# Comunicaciones.net
KiCad netlist of a schematic drawn in Altium Designer
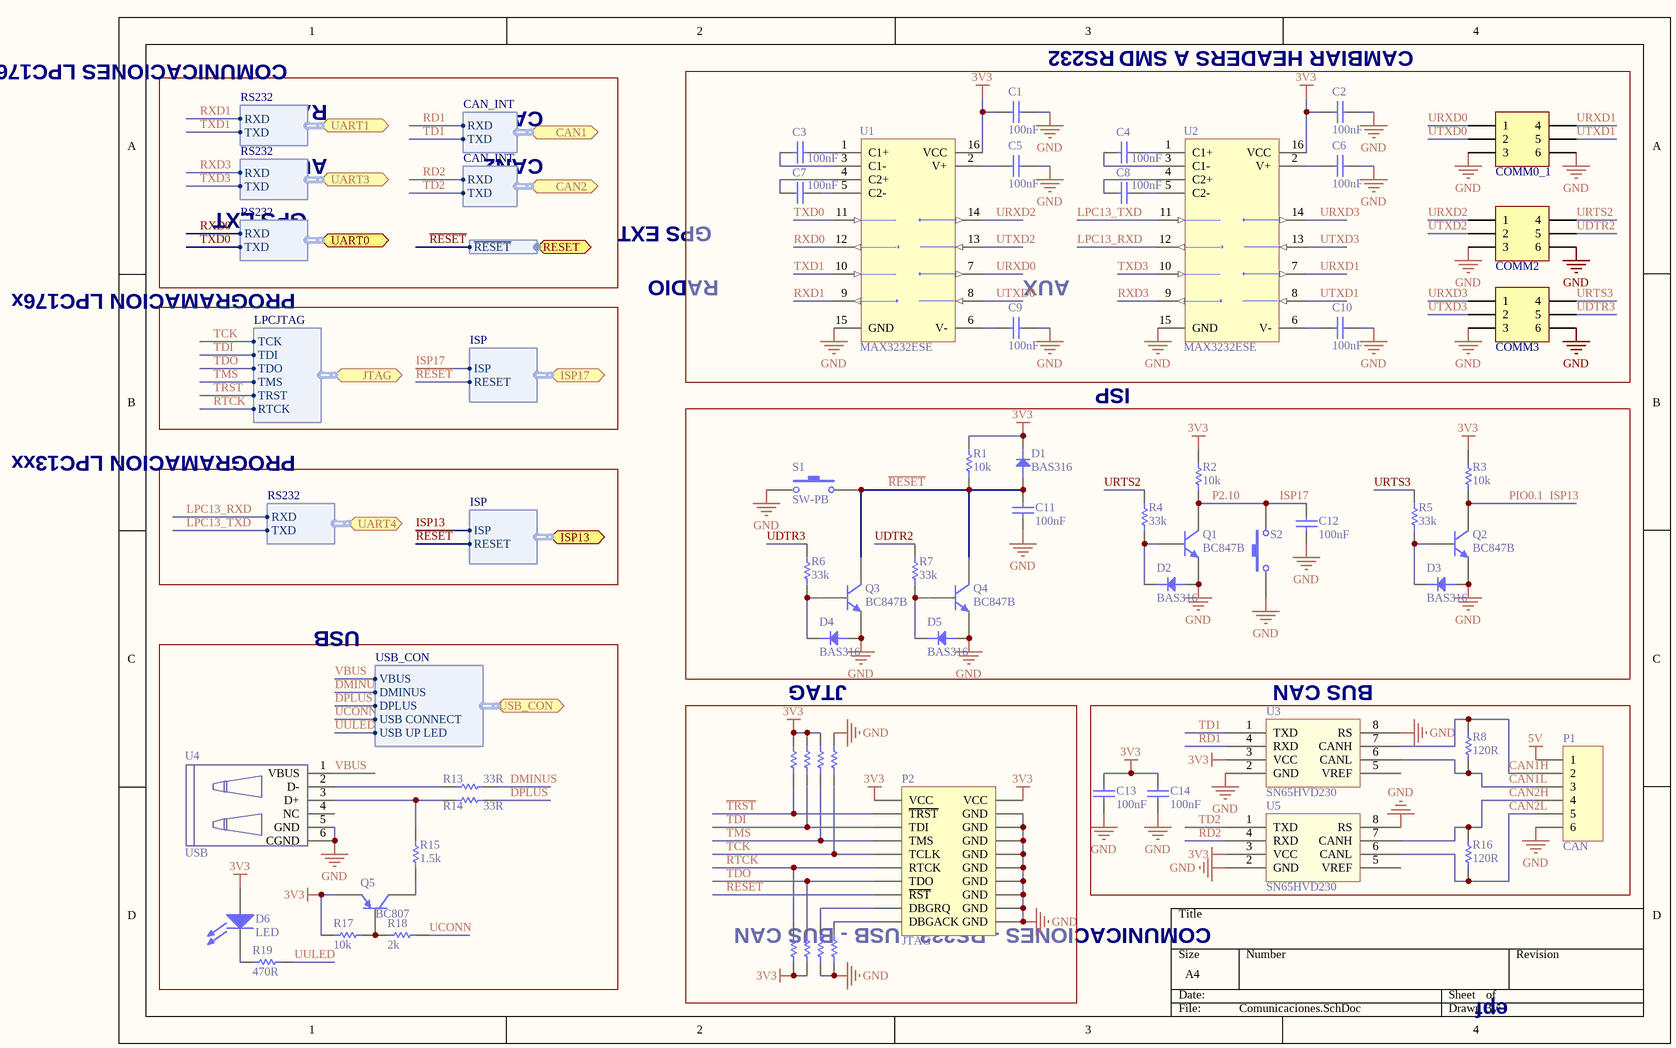
[diagram p0: Comunicaciones.SchDoc]

(export (version "E")
  (design (tool "Eeschema 10.0.6"))
  (components
    (comp (ref "C1")
      (value "100nF")
      (footprint "CAP0402")
      (fields (field (name "Comment") "Capacitor"))
      (libsource (lib "epf") (part "Cap"))
    )
    (comp (ref "C2")
      (value "100nF")
      (footprint "CAP0402")
      (fields (field (name "Comment") "Capacitor"))
      (libsource (lib "epf") (part "Cap"))
    )
    (comp (ref "C3")
      (value "100nF")
      (footprint "CAP0402")
      (fields (field (name "Comment") "Capacitor"))
      (libsource (lib "epf") (part "Cap"))
    )
    (comp (ref "C4")
      (value "100nF")
      (footprint "CAP0402")
      (fields (field (name "Comment") "Capacitor"))
      (libsource (lib "epf") (part "Cap"))
    )
    (comp (ref "C5")
      (value "100nF")
      (footprint "CAP0402")
      (fields (field (name "Comment") "Capacitor"))
      (libsource (lib "epf") (part "Cap"))
    )
    (comp (ref "C6")
      (value "100nF")
      (footprint "CAP0402")
      (fields (field (name "Comment") "Capacitor"))
      (libsource (lib "epf") (part "Cap"))
    )
    (comp (ref "C7")
      (value "100nF")
      (footprint "CAP0402")
      (fields (field (name "Comment") "Capacitor"))
      (libsource (lib "epf") (part "Cap"))
    )
    (comp (ref "C8")
      (value "100nF")
      (footprint "CAP0402")
      (fields (field (name "Comment") "Capacitor"))
      (libsource (lib "epf") (part "Cap"))
    )
    (comp (ref "C9")
      (value "100nF")
      (footprint "CAP0402")
      (fields (field (name "Comment") "Capacitor"))
      (libsource (lib "epf") (part "Cap"))
    )
    (comp (ref "C10")
      (value "100nF")
      (footprint "CAP0402")
      (fields (field (name "Comment") "Capacitor"))
      (libsource (lib "epf") (part "Cap"))
    )
    (comp (ref "C11")
      (value "100nF")
      (footprint "CAP0402")
      (fields (field (name "Comment") "Capacitor"))
      (libsource (lib "epf") (part "Cap"))
    )
    (comp (ref "C12")
      (value "100nF")
      (footprint "CAP0402")
      (fields (field (name "Comment") "Capacitor"))
      (libsource (lib "epf") (part "Cap"))
    )
    (comp (ref "C13")
      (value "100nF")
      (footprint "CAP0402")
      (fields (field (name "Comment") "Capacitor"))
      (libsource (lib "epf") (part "Cap"))
    )
    (comp (ref "C14")
      (value "100nF")
      (footprint "CAP0402")
      (fields (field (name "Comment") "Capacitor"))
      (libsource (lib "epf") (part "Cap"))
    )
    (comp (ref "COMM0_1")
      (value "AP_COMM")
      (footprint "HDR2X3_CEN")
      (description "Header, 3-Pin, Dual row")
      (fields (field (name "PUBLISHER") "Altium Limited"))
      (libsource (lib "epf") (part "AP_COMM"))
    )
    (comp (ref "COMM2")
      (value "AP_COMM")
      (footprint "HDR2X3_CEN")
      (description "Header, 3-Pin, Dual row")
      (fields (field (name "PUBLISHER") "Altium Limited"))
      (libsource (lib "epf") (part "AP_COMM"))
    )
    (comp (ref "COMM3")
      (value "AP_COMM")
      (footprint "HDR2X3_CEN")
      (description "Header, 3-Pin, Dual row")
      (fields (field (name "PUBLISHER") "Altium Limited"))
      (libsource (lib "epf") (part "AP_COMM"))
    )
    (comp (ref "D1") (value "BAS316") (footprint "SOD-323") (libsource (lib "epf") (part "BAS316")))
    (comp (ref "D2") (value "BAS316") (footprint "SOD-323") (libsource (lib "epf") (part "BAS316")))
    (comp (ref "D3") (value "BAS316") (footprint "SOD-323") (libsource (lib "epf") (part "BAS316")))
    (comp (ref "D4") (value "BAS316") (footprint "SOD-323") (libsource (lib "epf") (part "BAS316")))
    (comp (ref "D5") (value "BAS316") (footprint "SOD-323") (libsource (lib "epf") (part "BAS316")))
    (comp (ref "D6") (value "LED") (footprint "PLCC-2Rojo") (libsource (lib "epf") (part "LED1")))
    (comp (ref "P1")
      (value "CAN")
      (footprint "HDR1X6")
      (description "Header, 6-Pin")
      (fields (field (name "PUBLISHER") "Altium Limited"))
      (libsource (lib "epf") (part "CAN_Conn"))
    )
    (comp (ref "P2")
      (value "JTAG")
      (footprint "HDR2X10")
      (description "Header, 10-Pin, Dual row")
      (fields (field (name "PUBLISHER") "Altium Limited"))
      (libsource (lib "epf") (part "JTAG"))
    )
    (comp (ref "Q1")
      (value "BC847B")
      (footprint "SOT23")
      (description "NPN 100MHz")
      (libsource (lib "epf") (part "BC847B"))
    )
    (comp (ref "Q2")
      (value "BC847B")
      (footprint "SOT23")
      (description "NPN 100MHz")
      (libsource (lib "epf") (part "BC847B"))
    )
    (comp (ref "Q3")
      (value "BC847B")
      (footprint "SOT23")
      (description "NPN 100MHz")
      (libsource (lib "epf") (part "BC847B"))
    )
    (comp (ref "Q4")
      (value "BC847B")
      (footprint "SOT23")
      (description "NPN 100MHz")
      (libsource (lib "epf") (part "BC847B"))
    )
    (comp (ref "Q5")
      (value "BC807")
      (footprint "SOT23")
      (description "PNP 100MHz")
      (libsource (lib "epf") (part "BC807"))
    )
    (comp (ref "R1")
      (value "10k")
      (footprint "RES0402")
      (fields (field (name "Comment") "Resistor"))
      (libsource (lib "epf") (part "Res"))
    )
    (comp (ref "R2")
      (value "10k")
      (footprint "RES0402")
      (fields (field (name "Comment") "Resistor"))
      (libsource (lib "epf") (part "Res"))
    )
    (comp (ref "R3")
      (value "10k")
      (footprint "RES0402")
      (fields (field (name "Comment") "Resistor"))
      (libsource (lib "epf") (part "Res"))
    )
    (comp (ref "R4")
      (value "33k")
      (footprint "RES0402")
      (fields (field (name "Comment") "Resistor"))
      (libsource (lib "epf") (part "Res"))
    )
    (comp (ref "R5")
      (value "33k")
      (footprint "RES0402")
      (fields (field (name "Comment") "Resistor"))
      (libsource (lib "epf") (part "Res"))
    )
    (comp (ref "R6")
      (value "33k")
      (footprint "RES0402")
      (fields (field (name "Comment") "Resistor"))
      (libsource (lib "epf") (part "Res"))
    )
    (comp (ref "R7")
      (value "33k")
      (footprint "RES0402")
      (fields (field (name "Comment") "Resistor"))
      (libsource (lib "epf") (part "Res"))
    )
    (comp (ref "R8")
      (value "120R")
      (footprint "RES0402")
      (fields (field (name "Comment") "Resistor"))
      (libsource (lib "epf") (part "Res"))
    )
    (comp (ref "R9") (value "Resistor") (footprint "RES0402") (libsource (lib "epf") (part "Res")))
    (comp (ref "R10") (value "Resistor") (footprint "RES0402") (libsource (lib "epf") (part "Res")))
    (comp (ref "R11") (value "Resistor") (footprint "RES0402") (libsource (lib "epf") (part "Res")))
    (comp (ref "R12") (value "Resistor") (footprint "RES0402") (libsource (lib "epf") (part "Res")))
    (comp (ref "R13")
      (value "33R")
      (footprint "RES0402")
      (fields (field (name "Comment") "Resistor"))
      (libsource (lib "epf") (part "Res"))
    )
    (comp (ref "R14")
      (value "33R")
      (footprint "RES0402")
      (fields (field (name "Comment") "Resistor"))
      (libsource (lib "epf") (part "Res"))
    )
    (comp (ref "R15")
      (value "1.5k")
      (footprint "RES0402")
      (fields (field (name "Comment") "Resistor"))
      (libsource (lib "epf") (part "Res"))
    )
    (comp (ref "R16")
      (value "120R")
      (footprint "RES0402")
      (fields (field (name "Comment") "Resistor"))
      (libsource (lib "epf") (part "Res"))
    )
    (comp (ref "R17")
      (value "10k")
      (footprint "RES0402")
      (fields (field (name "Comment") "Resistor"))
      (libsource (lib "epf") (part "Res"))
    )
    (comp (ref "R18")
      (value "2k")
      (footprint "RES0402")
      (fields (field (name "Comment") "Resistor"))
      (libsource (lib "epf") (part "Res"))
    )
    (comp (ref "R19")
      (value "470R")
      (footprint "RES0402")
      (fields (field (name "Comment") "Resistor"))
      (libsource (lib "epf") (part "Res"))
    )
    (comp (ref "R20") (value "Resistor") (footprint "RES0402") (libsource (lib "epf") (part "Res")))
    (comp (ref "R21") (value "Resistor") (footprint "RES0402") (libsource (lib "epf") (part "Res")))
    (comp (ref "R22") (value "Resistor") (footprint "RES0402") (libsource (lib "epf") (part "Res")))
    (comp (ref "R23") (value "Resistor") (footprint "RES0402") (libsource (lib "epf") (part "Res")))
    (comp (ref "S1")
      (value "SW-PB")
      (footprint "SW-PB6mm - 2")
      (description "Switch")
      (fields (field (name "PUBLISHER") "Altium Limited"))
      (libsource (lib "epf") (part "SW-PB"))
    )
    (comp (ref "S2")
      (value "SW-PB")
      (footprint "SW-PB6mm - 2")
      (description "Switch")
      (fields (field (name "PUBLISHER") "Altium Limited"))
      (libsource (lib "epf") (part "SW-PB"))
    )
    (comp (ref "U1")
      (value "MAX3232ESE")
      (footprint "SOIC127P602-16BN")
      (libsource (lib "epf") (part "MAX3232ESE+"))
    )
    (comp (ref "U2")
      (value "MAX3232ESE")
      (footprint "SOIC127P602-16BN")
      (libsource (lib "epf") (part "MAX3232ESE+"))
    )
    (comp (ref "U3")
      (value "SN65HVD230")
      (footprint "SOIC127P600-8CN")
      (description "3.3-V CAN TRANSCEIVERS")
      (libsource (lib "epf") (part "SN65HVD230"))
    )
    (comp (ref "U4") (value "USB") (footprint "USB/SM0.8-6H5") (libsource (lib "epf") (part "USB-miniB")))
    (comp (ref "U5")
      (value "SN65HVD230")
      (footprint "SOIC127P600-8CN")
      (description "3.3-V CAN TRANSCEIVERS")
      (libsource (lib "epf") (part "SN65HVD230"))
    )
  )
  (nets
    (net (code "6") (name "/CAN1H") (class "Default")
      (node (ref "P1") (pin "2") (pinfunction "2_2") (pintype "passive"))
      (node (ref "R8") (pin "1") (pinfunction "1_1") (pintype "passive"))
      (node (ref "U3") (pin "7") (pinfunction "CANH_7") (pintype "passive"))
    )
    (net (code "7") (name "/CAN1L") (class "Default")
      (node (ref "P1") (pin "3") (pinfunction "3_3") (pintype "passive"))
      (node (ref "R8") (pin "2") (pinfunction "2_2") (pintype "passive"))
      (node (ref "U3") (pin "6") (pinfunction "CANL_6") (pintype "passive"))
    )
    (net (code "8") (name "/CAN2H") (class "Default")
      (node (ref "P1") (pin "4") (pinfunction "4_4") (pintype "passive"))
      (node (ref "R16") (pin "1") (pinfunction "1_1") (pintype "passive"))
      (node (ref "U5") (pin "7") (pinfunction "CANH_7") (pintype "passive"))
    )
    (net (code "9") (name "/CAN2L") (class "Default")
      (node (ref "P1") (pin "5") (pinfunction "5_5") (pintype "passive"))
      (node (ref "R16") (pin "2") (pinfunction "2_2") (pintype "passive"))
      (node (ref "U5") (pin "6") (pinfunction "CANL_6") (pintype "passive"))
    )
    (net (code "10") (name "/DMINUS") (class "Default")
      (node (ref "R13") (pin "2") (pinfunction "2_2") (pintype "passive"))
    )
    (net (code "11") (name "/DPLUS") (class "Default")
      (node (ref "R14") (pin "2") (pinfunction "2_2") (pintype "passive"))
    )
    (net (code "12") (name "/ISP13") (class "Default")
      (node (ref "Q2") (pin "3") (pinfunction "C_3") (pintype "passive"))
      (node (ref "R3") (pin "1") (pinfunction "1_1") (pintype "passive"))
    )
    (net (code "13") (name "/ISP17") (class "Default")
      (node (ref "C12") (pin "1") (pinfunction "1_1") (pintype "passive"))
      (node (ref "Q1") (pin "3") (pinfunction "C_3") (pintype "passive"))
      (node (ref "R2") (pin "1") (pinfunction "1_1") (pintype "passive"))
      (node (ref "S2") (pin "2") (pinfunction "2_2") (pintype "passive"))
    )
    (net (code "14") (name "/LPC13_RXD") (class "Default")
      (node (ref "U2") (pin "12") (pinfunction "R1OUT_12") (pintype "output"))
    )
    (net (code "15") (name "/LPC13_TXD") (class "Default")
      (node (ref "U2") (pin "11") (pinfunction "T1IN_11") (pintype "input"))
    )
    (net (code "16") (name "/RD1") (class "Default")
      (node (ref "U3") (pin "4") (pinfunction "RXD_4") (pintype "passive"))
    )
    (net (code "17") (name "/RD2") (class "Default")
      (node (ref "U5") (pin "4") (pinfunction "RXD_4") (pintype "passive"))
    )
    (net (code "18") (name "/RESET") (class "Default")
      (node (ref "C11") (pin "1") (pinfunction "1_1") (pintype "passive"))
      (node (ref "D1") (pin "2") (pinfunction "A_2") (pintype "passive"))
      (node (ref "P2") (pin "15") (pinfunction "RST_15") (pintype "passive"))
      (node (ref "Q3") (pin "3") (pinfunction "C_3") (pintype "passive"))
      (node (ref "Q4") (pin "3") (pinfunction "C_3") (pintype "passive"))
      (node (ref "R1") (pin "1") (pinfunction "1_1") (pintype "passive"))
      (node (ref "S1") (pin "2") (pinfunction "2_2") (pintype "passive"))
    )
    (net (code "19") (name "/RTCK") (class "Default")
      (node (ref "P2") (pin "11") (pinfunction "RTCK_11") (pintype "passive"))
      (node (ref "R20") (pin "1") (pinfunction "1_1") (pintype "passive"))
    )
    (net (code "20") (name "/RXD0") (class "Default")
      (node (ref "U1") (pin "12") (pinfunction "R1OUT_12") (pintype "output"))
    )
    (net (code "21") (name "/RXD1") (class "Default")
      (node (ref "U1") (pin "9") (pinfunction "R2OUT_9") (pintype "output"))
    )
    (net (code "22") (name "/RXD3") (class "Default")
      (node (ref "U2") (pin "9") (pinfunction "R2OUT_9") (pintype "output"))
    )
    (net (code "23") (name "/TCK") (class "Default")
      (node (ref "P2") (pin "9") (pinfunction "TCLK_9") (pintype "passive"))
      (node (ref "R12") (pin "2") (pinfunction "2_2") (pintype "passive"))
    )
    (net (code "24") (name "/TD1") (class "Default")
      (node (ref "U3") (pin "1") (pinfunction "TXD_1") (pintype "passive"))
    )
    (net (code "25") (name "/TD2") (class "Default")
      (node (ref "U5") (pin "1") (pinfunction "TXD_1") (pintype "passive"))
    )
    (net (code "26") (name "/TDI") (class "Default")
      (node (ref "P2") (pin "5") (pinfunction "TDI_5") (pintype "passive"))
      (node (ref "R10") (pin "2") (pinfunction "2_2") (pintype "passive"))
    )
    (net (code "27") (name "/TDO") (class "Default")
      (node (ref "P2") (pin "13") (pinfunction "TDO_13") (pintype "passive"))
      (node (ref "R21") (pin "1") (pinfunction "1_1") (pintype "passive"))
    )
    (net (code "28") (name "/TMS") (class "Default")
      (node (ref "P2") (pin "7") (pinfunction "TMS_7") (pintype "passive"))
      (node (ref "R11") (pin "2") (pinfunction "2_2") (pintype "passive"))
    )
    (net (code "29") (name "/TRST") (class "Default")
      (node (ref "P2") (pin "3") (pinfunction "TRST_3") (pintype "passive"))
      (node (ref "R9") (pin "2") (pinfunction "2_2") (pintype "passive"))
    )
    (net (code "30") (name "/TXD0") (class "Default")
      (node (ref "U1") (pin "11") (pinfunction "T1IN_11") (pintype "input"))
    )
    (net (code "31") (name "/TXD1") (class "Default")
      (node (ref "U1") (pin "10") (pinfunction "T2IN_10") (pintype "input"))
    )
    (net (code "32") (name "/TXD3") (class "Default")
      (node (ref "U2") (pin "10") (pinfunction "T2IN_10") (pintype "input"))
    )
    (net (code "33") (name "/UCONN") (class "Default")
      (node (ref "R18") (pin "2") (pinfunction "2_2") (pintype "passive"))
    )
    (net (code "34") (name "/UDTR2") (class "Default")
      (node (ref "COMM2") (pin "5") (pinfunction "5_5") (pintype "passive"))
      (node (ref "R7") (pin "2") (pinfunction "2_2") (pintype "passive"))
    )
    (net (code "35") (name "/UDTR3") (class "Default")
      (node (ref "COMM3") (pin "5") (pinfunction "5_5") (pintype "passive"))
      (node (ref "R6") (pin "2") (pinfunction "2_2") (pintype "passive"))
    )
    (net (code "36") (name "/URTS2") (class "Default")
      (node (ref "COMM2") (pin "4") (pinfunction "4_4") (pintype "passive"))
      (node (ref "R4") (pin "2") (pinfunction "2_2") (pintype "passive"))
    )
    (net (code "37") (name "/URTS3") (class "Default")
      (node (ref "COMM3") (pin "4") (pinfunction "4_4") (pintype "passive"))
      (node (ref "R5") (pin "2") (pinfunction "2_2") (pintype "passive"))
    )
    (net (code "38") (name "/URXD0") (class "Default")
      (node (ref "COMM0_1") (pin "1") (pinfunction "1_1") (pintype "passive"))
      (node (ref "U1") (pin "7") (pinfunction "T2OUT_7") (pintype "output"))
    )
    (net (code "39") (name "/URXD1") (class "Default")
      (node (ref "COMM0_1") (pin "4") (pinfunction "4_4") (pintype "passive"))
      (node (ref "U2") (pin "7") (pinfunction "T2OUT_7") (pintype "output"))
    )
    (net (code "40") (name "/URXD2") (class "Default")
      (node (ref "COMM2") (pin "1") (pinfunction "1_1") (pintype "passive"))
      (node (ref "U1") (pin "14") (pinfunction "T1OUT_14") (pintype "output"))
    )
    (net (code "41") (name "/URXD3") (class "Default")
      (node (ref "COMM3") (pin "1") (pinfunction "1_1") (pintype "passive"))
      (node (ref "U2") (pin "14") (pinfunction "T1OUT_14") (pintype "output"))
    )
    (net (code "42") (name "/UTXD0") (class "Default")
      (node (ref "COMM0_1") (pin "2") (pinfunction "2_2") (pintype "passive"))
      (node (ref "U1") (pin "8") (pinfunction "R2IN_8") (pintype "input"))
    )
    (net (code "43") (name "/UTXD1") (class "Default")
      (node (ref "COMM0_1") (pin "5") (pinfunction "5_5") (pintype "passive"))
      (node (ref "U2") (pin "8") (pinfunction "R2IN_8") (pintype "input"))
    )
    (net (code "44") (name "/UTXD2") (class "Default")
      (node (ref "COMM2") (pin "2") (pinfunction "2_2") (pintype "passive"))
      (node (ref "U1") (pin "13") (pinfunction "R1IN_13") (pintype "input"))
    )
    (net (code "45") (name "/UTXD3") (class "Default")
      (node (ref "COMM3") (pin "2") (pinfunction "2_2") (pintype "passive"))
      (node (ref "U2") (pin "13") (pinfunction "R1IN_13") (pintype "input"))
    )
    (net (code "46") (name "/UULED") (class "Default")
      (node (ref "R19") (pin "2") (pinfunction "2_2") (pintype "passive"))
    )
    (net (code "47") (name "/VBUS") (class "Default")
      (node (ref "U4") (pin "1") (pinfunction "VBUS_1") (pintype "passive"))
    )
    (net (code "54") (name "3V3") (class "Default")
      (node (ref "C1") (pin "2") (pinfunction "2_2") (pintype "passive"))
      (node (ref "C13") (pin "2") (pinfunction "2_2") (pintype "passive"))
      (node (ref "C14") (pin "2") (pinfunction "2_2") (pintype "passive"))
      (node (ref "C2") (pin "2") (pinfunction "2_2") (pintype "passive"))
      (node (ref "D1") (pin "1") (pinfunction "K_1") (pintype "passive"))
      (node (ref "D6") (pin "1") (pinfunction "A_1") (pintype "passive"))
      (node (ref "P2") (pin "1") (pinfunction "VCC_1") (pintype "passive"))
      (node (ref "P2") (pin "2") (pinfunction "VCC_2") (pintype "passive"))
      (node (ref "Q5") (pin "2") (pinfunction "E_2") (pintype "passive"))
      (node (ref "R1") (pin "2") (pinfunction "2_2") (pintype "passive"))
      (node (ref "R10") (pin "1") (pinfunction "1_1") (pintype "passive"))
      (node (ref "R11") (pin "1") (pinfunction "1_1") (pintype "passive"))
      (node (ref "R17") (pin "1") (pinfunction "1_1") (pintype "passive"))
      (node (ref "R2") (pin "2") (pinfunction "2_2") (pintype "passive"))
      (node (ref "R20") (pin "2") (pinfunction "2_2") (pintype "passive"))
      (node (ref "R21") (pin "2") (pinfunction "2_2") (pintype "passive"))
      (node (ref "R3") (pin "2") (pinfunction "2_2") (pintype "passive"))
      (node (ref "R9") (pin "1") (pinfunction "1_1") (pintype "passive"))
      (node (ref "U1") (pin "16") (pinfunction "VCC_16") (pintype "power_in"))
      (node (ref "U2") (pin "16") (pinfunction "VCC_16") (pintype "power_in"))
      (node (ref "U3") (pin "3") (pinfunction "VCC_3") (pintype "passive"))
      (node (ref "U5") (pin "3") (pinfunction "VCC_3") (pintype "passive"))
    )
    (net (code "55") (name "5V") (class "Default")
      (node (ref "P1") (pin "1") (pinfunction "1_1") (pintype "passive"))
    )
    (net (code "56") (name "GND") (class "Default")
      (node (ref "C1") (pin "1") (pinfunction "1_1") (pintype "passive"))
      (node (ref "C10") (pin "1") (pinfunction "1_1") (pintype "passive"))
      (node (ref "C11") (pin "2") (pinfunction "2_2") (pintype "passive"))
      (node (ref "C12") (pin "2") (pinfunction "2_2") (pintype "passive"))
      (node (ref "C13") (pin "1") (pinfunction "1_1") (pintype "passive"))
      (node (ref "C14") (pin "1") (pinfunction "1_1") (pintype "passive"))
      (node (ref "C2") (pin "1") (pinfunction "1_1") (pintype "passive"))
      (node (ref "C5") (pin "1") (pinfunction "1_1") (pintype "passive"))
      (node (ref "C6") (pin "1") (pinfunction "1_1") (pintype "passive"))
      (node (ref "C9") (pin "1") (pinfunction "1_1") (pintype "passive"))
      (node (ref "COMM0_1") (pin "3") (pinfunction "3_3") (pintype "passive"))
      (node (ref "COMM0_1") (pin "6") (pinfunction "6_6") (pintype "passive"))
      (node (ref "COMM2") (pin "3") (pinfunction "3_3") (pintype "passive"))
      (node (ref "COMM2") (pin "6") (pinfunction "6_6") (pintype "passive"))
      (node (ref "COMM3") (pin "3") (pinfunction "3_3") (pintype "passive"))
      (node (ref "COMM3") (pin "6") (pinfunction "6_6") (pintype "passive"))
      (node (ref "D2") (pin "2") (pinfunction "A_2") (pintype "passive"))
      (node (ref "D3") (pin "2") (pinfunction "A_2") (pintype "passive"))
      (node (ref "D4") (pin "2") (pinfunction "A_2") (pintype "passive"))
      (node (ref "D5") (pin "2") (pinfunction "A_2") (pintype "passive"))
      (node (ref "P1") (pin "6") (pinfunction "6_6") (pintype "passive"))
      (node (ref "P2") (pin "10") (pinfunction "GND_10") (pintype "passive"))
      (node (ref "P2") (pin "12") (pinfunction "GND_12") (pintype "passive"))
      (node (ref "P2") (pin "14") (pinfunction "GND_14") (pintype "passive"))
      (node (ref "P2") (pin "16") (pinfunction "GND_16") (pintype "passive"))
      (node (ref "P2") (pin "18") (pinfunction "GND_18") (pintype "passive"))
      (node (ref "P2") (pin "20") (pinfunction "GND_20") (pintype "passive"))
      (node (ref "P2") (pin "4") (pinfunction "GND_4") (pintype "passive"))
      (node (ref "P2") (pin "6") (pinfunction "GND_6") (pintype "passive"))
      (node (ref "P2") (pin "8") (pinfunction "GND_8") (pintype "passive"))
      (node (ref "Q1") (pin "2") (pinfunction "E_2") (pintype "passive"))
      (node (ref "Q2") (pin "2") (pinfunction "E_2") (pintype "passive"))
      (node (ref "Q3") (pin "2") (pinfunction "E_2") (pintype "passive"))
      (node (ref "Q4") (pin "2") (pinfunction "E_2") (pintype "passive"))
      (node (ref "R12") (pin "1") (pinfunction "1_1") (pintype "passive"))
      (node (ref "R22") (pin "2") (pinfunction "2_2") (pintype "passive"))
      (node (ref "R23") (pin "2") (pinfunction "2_2") (pintype "passive"))
      (node (ref "S1") (pin "1") (pinfunction "1_1") (pintype "passive"))
      (node (ref "S2") (pin "1") (pinfunction "1_1") (pintype "passive"))
      (node (ref "U1") (pin "15") (pinfunction "GND_15") (pintype "power_in"))
      (node (ref "U2") (pin "15") (pinfunction "GND_15") (pintype "power_in"))
      (node (ref "U3") (pin "2") (pinfunction "GND_2") (pintype "passive"))
      (node (ref "U3") (pin "8") (pinfunction "RS_8") (pintype "passive"))
      (node (ref "U4") (pin "5") (pinfunction "GND_5") (pintype "passive"))
      (node (ref "U4") (pin "6") (pinfunction "CGND_6") (pintype "passive"))
      (node (ref "U5") (pin "2") (pinfunction "GND_2") (pintype "passive"))
      (node (ref "U5") (pin "8") (pinfunction "RS_8") (pintype "passive"))
    )
    (net (code "57") (name "Net-(D2-K)") (class "Default")
      (node (ref "D2") (pin "1") (pinfunction "K_1") (pintype "passive"))
      (node (ref "Q1") (pin "1") (pinfunction "B_1") (pintype "passive"))
      (node (ref "R4") (pin "1") (pinfunction "1_1") (pintype "passive"))
    )
    (net (code "58") (name "Net-(D3-K)") (class "Default")
      (node (ref "D3") (pin "1") (pinfunction "K_1") (pintype "passive"))
      (node (ref "Q2") (pin "1") (pinfunction "B_1") (pintype "passive"))
      (node (ref "R5") (pin "1") (pinfunction "1_1") (pintype "passive"))
    )
    (net (code "59") (name "Net-(D4-K)") (class "Default")
      (node (ref "D4") (pin "1") (pinfunction "K_1") (pintype "passive"))
      (node (ref "Q3") (pin "1") (pinfunction "B_1") (pintype "passive"))
      (node (ref "R6") (pin "1") (pinfunction "1_1") (pintype "passive"))
    )
    (net (code "60") (name "Net-(D5-K)") (class "Default")
      (node (ref "D5") (pin "1") (pinfunction "K_1") (pintype "passive"))
      (node (ref "Q4") (pin "1") (pinfunction "B_1") (pintype "passive"))
      (node (ref "R7") (pin "1") (pinfunction "1_1") (pintype "passive"))
    )
    (net (code "61") (name "Net-(D6-K)") (class "Default")
      (node (ref "D6") (pin "2") (pinfunction "K_2") (pintype "passive"))
      (node (ref "R19") (pin "1") (pinfunction "1_1") (pintype "passive"))
    )
    (net (code "62") (name "Net-(P2-DBGACK)") (class "Default")
      (node (ref "P2") (pin "19") (pinfunction "DBGACK_19") (pintype "passive"))
      (node (ref "R23") (pin "1") (pinfunction "1_1") (pintype "passive"))
    )
    (net (code "63") (name "Net-(P2-DBGRQ)") (class "Default")
      (node (ref "P2") (pin "17") (pinfunction "DBGRQ_17") (pintype "passive"))
      (node (ref "R22") (pin "1") (pinfunction "1_1") (pintype "passive"))
    )
    (net (code "64") (name "Net-(Q5-B)") (class "Default")
      (node (ref "Q5") (pin "1") (pinfunction "B_1") (pintype "passive"))
      (node (ref "R17") (pin "2") (pinfunction "2_2") (pintype "passive"))
      (node (ref "R18") (pin "1") (pinfunction "1_1") (pintype "passive"))
    )
    (net (code "65") (name "Net-(Q5-C)") (class "Default")
      (node (ref "Q5") (pin "3") (pinfunction "C_3") (pintype "passive"))
      (node (ref "R15") (pin "2") (pinfunction "2_2") (pintype "passive"))
    )
    (net (code "66") (name "Net-(U1-C1+)") (class "Default")
      (node (ref "C3") (pin "1") (pinfunction "1_1") (pintype "passive"))
      (node (ref "U1") (pin "1") (pinfunction "C1+_1") (pintype "passive"))
    )
    (net (code "67") (name "Net-(U1-C1-)") (class "Default")
      (node (ref "C3") (pin "2") (pinfunction "2_2") (pintype "passive"))
      (node (ref "U1") (pin "3") (pinfunction "C1-_3") (pintype "passive"))
    )
    (net (code "68") (name "Net-(U1-C2+)") (class "Default")
      (node (ref "C7") (pin "2") (pinfunction "2_2") (pintype "passive"))
      (node (ref "U1") (pin "4") (pinfunction "C2+_4") (pintype "passive"))
    )
    (net (code "69") (name "Net-(U1-C2-)") (class "Default")
      (node (ref "C7") (pin "1") (pinfunction "1_1") (pintype "passive"))
      (node (ref "U1") (pin "5") (pinfunction "C2-_5") (pintype "passive"))
    )
    (net (code "70") (name "Net-(U1-V+)") (class "Default")
      (node (ref "C5") (pin "2") (pinfunction "2_2") (pintype "passive"))
      (node (ref "U1") (pin "2") (pinfunction "V+_2") (pintype "power_in"))
    )
    (net (code "71") (name "Net-(U1-V-)") (class "Default")
      (node (ref "C9") (pin "2") (pinfunction "2_2") (pintype "passive"))
      (node (ref "U1") (pin "6") (pinfunction "V-_6") (pintype "power_in"))
    )
    (net (code "72") (name "Net-(U2-C1+)") (class "Default")
      (node (ref "C4") (pin "1") (pinfunction "1_1") (pintype "passive"))
      (node (ref "U2") (pin "1") (pinfunction "C1+_1") (pintype "passive"))
    )
    (net (code "73") (name "Net-(U2-C1-)") (class "Default")
      (node (ref "C4") (pin "2") (pinfunction "2_2") (pintype "passive"))
      (node (ref "U2") (pin "3") (pinfunction "C1-_3") (pintype "passive"))
    )
    (net (code "74") (name "Net-(U2-C2+)") (class "Default")
      (node (ref "C8") (pin "2") (pinfunction "2_2") (pintype "passive"))
      (node (ref "U2") (pin "4") (pinfunction "C2+_4") (pintype "passive"))
    )
    (net (code "75") (name "Net-(U2-C2-)") (class "Default")
      (node (ref "C8") (pin "1") (pinfunction "1_1") (pintype "passive"))
      (node (ref "U2") (pin "5") (pinfunction "C2-_5") (pintype "passive"))
    )
    (net (code "76") (name "Net-(U2-V+)") (class "Default")
      (node (ref "C6") (pin "2") (pinfunction "2_2") (pintype "passive"))
      (node (ref "U2") (pin "2") (pinfunction "V+_2") (pintype "power_in"))
    )
    (net (code "77") (name "Net-(U2-V-)") (class "Default")
      (node (ref "C10") (pin "2") (pinfunction "2_2") (pintype "passive"))
      (node (ref "U2") (pin "6") (pinfunction "V-_6") (pintype "power_in"))
    )
    (net (code "78") (name "Net-(U4-D+)") (class "Default")
      (node (ref "R14") (pin "1") (pinfunction "1_1") (pintype "passive"))
      (node (ref "R15") (pin "1") (pinfunction "1_1") (pintype "passive"))
      (node (ref "U4") (pin "3") (pinfunction "D+_3") (pintype "passive"))
    )
    (net (code "79") (name "Net-(U4-D-)") (class "Default")
      (node (ref "R13") (pin "1") (pinfunction "1_1") (pintype "passive"))
      (node (ref "U4") (pin "2") (pinfunction "D-_2") (pintype "passive"))
    )
    (net (code "80") (name "unconnected-(U3-VREF-Pad5)") (class "Default")
      (node (ref "U3") (pin "5") (pinfunction "VREF_5") (pintype "passive"))
    )
    (net (code "81") (name "unconnected-(U4-NC-Pad4)") (class "Default")
      (node (ref "U4") (pin "4") (pinfunction "NC_4") (pintype "passive"))
    )
    (net (code "82") (name "unconnected-(U5-VREF-Pad5)") (class "Default")
      (node (ref "U5") (pin "5") (pinfunction "VREF_5") (pintype "passive"))
    )
  )
)
